# DriverMosfet_2.net
KiCad netlist of a schematic drawn in EAGLE
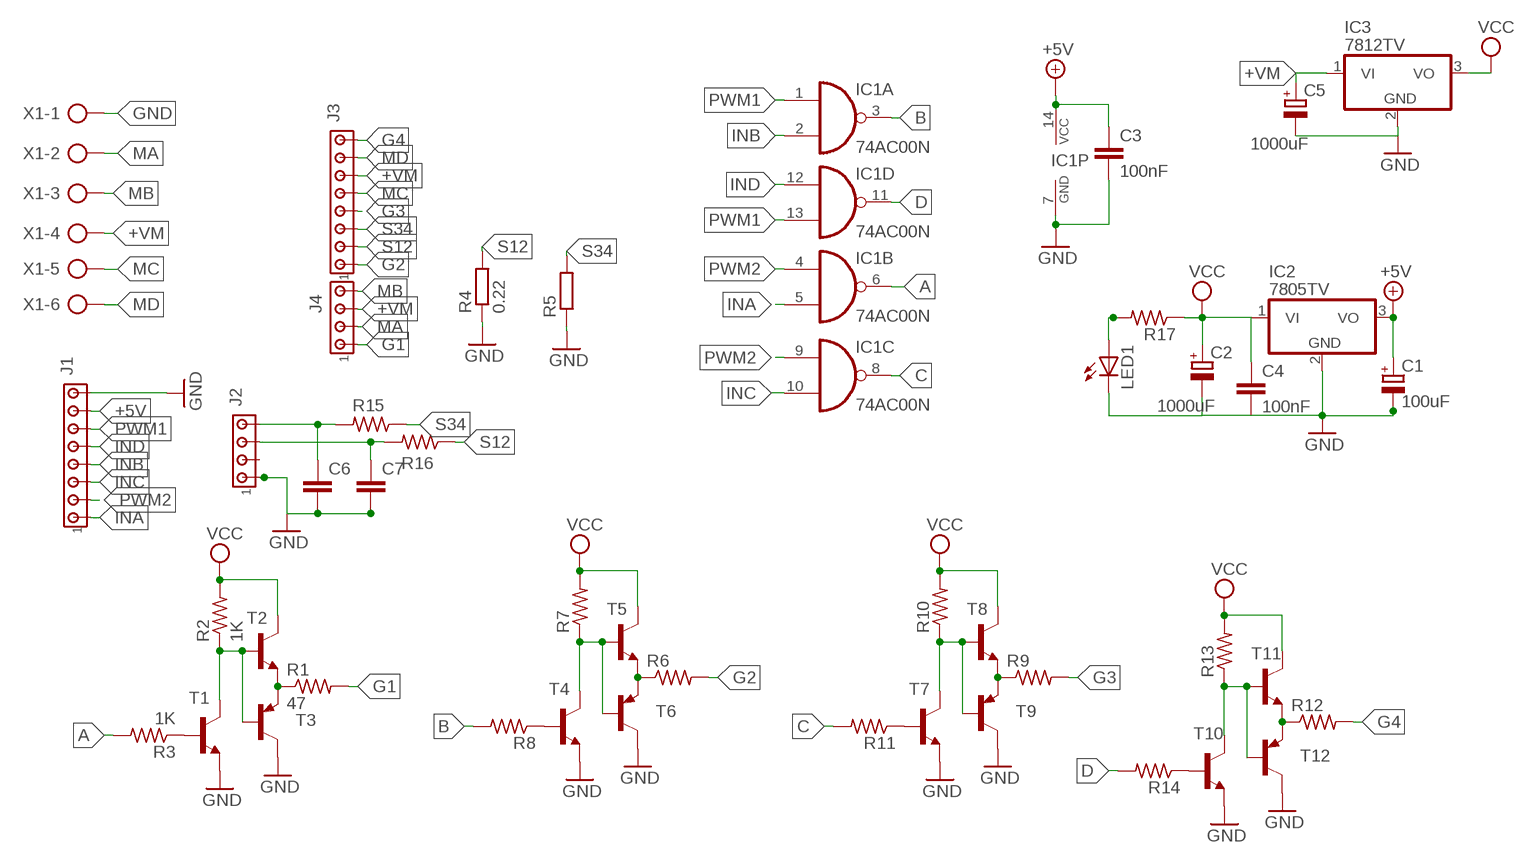
[diagram p0: schematic, sheet 1]

(export (version "E")
  (design (tool "Eeschema 10.0.6"))
  (components
    (comp (ref "C1")
      (value "100uF")
      (footprint "eagle-import:E2,5-6")
      (libsource (lib "eagle-import") (part "CPOL-EUE2.5-6"))
    )
    (comp (ref "C2")
      (value "1000uF")
      (footprint "eagle-import:E2,5-7")
      (libsource (lib "eagle-import") (part "CPOL-EUE2.5-7"))
    )
    (comp (ref "C3")
      (value "100nF")
      (footprint "eagle-import:C050-025X075")
      (libsource (lib "eagle-import") (part "C-EU050-025X075"))
    )
    (comp (ref "C4")
      (value "100nF")
      (footprint "eagle-import:C050-025X075")
      (libsource (lib "eagle-import") (part "C-EU050-025X075"))
    )
    (comp (ref "C5")
      (value "1000uF")
      (footprint "eagle-import:E3,5-10")
      (libsource (lib "eagle-import") (part "CPOL-EUE3.5-10"))
    )
    (comp (ref "C6")
      (value "C-EU025-030X050")
      (footprint "eagle-import:C025-030X050")
      (libsource (lib "eagle-import") (part "C-EU025-030X050"))
    )
    (comp (ref "C7")
      (value "C-EU025-030X050")
      (footprint "eagle-import:C025-030X050")
      (libsource (lib "eagle-import") (part "C-EU025-030X050"))
    )
    (comp (ref "IC1")
      (value "74AC00N")
      (footprint "eagle-import:DIL14")
      (libsource (lib "eagle-import") (part "7400NAC"))
    )
    (comp (ref "IC2")
      (value "7805TV")
      (footprint "eagle-import:TO220V")
      (libsource (lib "eagle-import") (part "78TV05"))
    )
    (comp (ref "IC3")
      (value "7812TV")
      (footprint "eagle-import:TO220V")
      (libsource (lib "eagle-import") (part "78TV12"))
    )
    (comp (ref "J1")
      (value "MTA08-100")
      (footprint "eagle-import:10X08MTA")
      (libsource (lib "eagle-import") (part "MTA08-100"))
    )
    (comp (ref "J2")
      (value "MTA04-100")
      (footprint "eagle-import:10X04MTA")
      (libsource (lib "eagle-import") (part "MTA04-100"))
    )
    (comp (ref "J3")
      (value "MTA08-100")
      (footprint "eagle-import:10X08MTA")
      (libsource (lib "eagle-import") (part "MTA08-100"))
    )
    (comp (ref "J4")
      (value "MTA04-100")
      (footprint "eagle-import:10X04MTA")
      (libsource (lib "eagle-import") (part "MTA04-100"))
    )
    (comp (ref "LED1")
      (value "LED3MM")
      (footprint "eagle-import:LED3MM")
      (libsource (lib "eagle-import") (part "LED3MM"))
    )
    (comp (ref "R1")
      (value "47")
      (footprint "eagle-import:0207_7")
      (libsource (lib "eagle-import") (part "R-US_0207/7"))
    )
    (comp (ref "R2")
      (value "1K")
      (footprint "eagle-import:0207_7")
      (libsource (lib "eagle-import") (part "R-US_0207/7"))
    )
    (comp (ref "R3")
      (value "1K")
      (footprint "eagle-import:0207_7")
      (libsource (lib "eagle-import") (part "R-US_0207/7"))
    )
    (comp (ref "R4")
      (value "0.22")
      (footprint "eagle-import:P0613_15")
      (libsource (lib "eagle-import") (part "R-EU_0613/15"))
    )
    (comp (ref "R5")
      (value "R-EU_0414/15")
      (footprint "eagle-import:0414_15")
      (libsource (lib "eagle-import") (part "R-EU_0414/15"))
    )
    (comp (ref "R6")
      (value "R-US_0207/7")
      (footprint "eagle-import:0207_7")
      (libsource (lib "eagle-import") (part "R-US_0207/7"))
    )
    (comp (ref "R7")
      (value "R-US_0207/7")
      (footprint "eagle-import:0207_7")
      (libsource (lib "eagle-import") (part "R-US_0207/7"))
    )
    (comp (ref "R8")
      (value "R-US_0207/7")
      (footprint "eagle-import:0207_7")
      (libsource (lib "eagle-import") (part "R-US_0207/7"))
    )
    (comp (ref "R9")
      (value "R-US_0207/7")
      (footprint "eagle-import:0207_7")
      (libsource (lib "eagle-import") (part "R-US_0207/7"))
    )
    (comp (ref "R10")
      (value "R-US_0207/7")
      (footprint "eagle-import:0207_7")
      (libsource (lib "eagle-import") (part "R-US_0207/7"))
    )
    (comp (ref "R11")
      (value "R-US_0207/7")
      (footprint "eagle-import:0207_7")
      (libsource (lib "eagle-import") (part "R-US_0207/7"))
    )
    (comp (ref "R12")
      (value "R-US_0207/7")
      (footprint "eagle-import:0207_7")
      (libsource (lib "eagle-import") (part "R-US_0207/7"))
    )
    (comp (ref "R13")
      (value "R-US_0207/7")
      (footprint "eagle-import:0207_7")
      (libsource (lib "eagle-import") (part "R-US_0207/7"))
    )
    (comp (ref "R14")
      (value "R-US_0207/7")
      (footprint "eagle-import:0207_7")
      (libsource (lib "eagle-import") (part "R-US_0207/7"))
    )
    (comp (ref "R15")
      (value "R-US_0207/7")
      (footprint "eagle-import:0207_7")
      (libsource (lib "eagle-import") (part "R-US_0207/7"))
    )
    (comp (ref "R16")
      (value "R-US_0207/7")
      (footprint "eagle-import:0207_7")
      (libsource (lib "eagle-import") (part "R-US_0207/7"))
    )
    (comp (ref "R17")
      (value "R-US_0207/7")
      (footprint "eagle-import:0207_7")
      (libsource (lib "eagle-import") (part "R-US_0207/7"))
    )
    (comp (ref "T1")
      (value "BC547-NPN-TO92-CBE")
      (footprint "eagle-import:TO92-CBE")
      (libsource (lib "eagle-import") (part "-NPN-TO92-CBEBC547"))
    )
    (comp (ref "T2")
      (value "BC547-NPN-TO92-CBE")
      (footprint "eagle-import:TO92-CBE")
      (libsource (lib "eagle-import") (part "-NPN-TO92-CBEBC547"))
    )
    (comp (ref "T3")
      (value "BC557A-PNP-TO92-EBC")
      (footprint "eagle-import:TO92-EBC")
      (libsource (lib "eagle-import") (part "-PNP-TO92-EBCBC557A"))
    )
    (comp (ref "T4")
      (value "BC547-NPN-TO92-CBE")
      (footprint "eagle-import:TO92-CBE")
      (libsource (lib "eagle-import") (part "-NPN-TO92-CBEBC547"))
    )
    (comp (ref "T5")
      (value "BC547-NPN-TO92-CBE")
      (footprint "eagle-import:TO92-CBE")
      (libsource (lib "eagle-import") (part "-NPN-TO92-CBEBC547"))
    )
    (comp (ref "T6")
      (value "BC557A-PNP-TO92-EBC")
      (footprint "eagle-import:TO92-EBC")
      (libsource (lib "eagle-import") (part "-PNP-TO92-EBCBC557A"))
    )
    (comp (ref "T7")
      (value "BC547-NPN-TO92-CBE")
      (footprint "eagle-import:TO92-CBE")
      (libsource (lib "eagle-import") (part "-NPN-TO92-CBEBC547"))
    )
    (comp (ref "T8")
      (value "BC547-NPN-TO92-CBE")
      (footprint "eagle-import:TO92-CBE")
      (libsource (lib "eagle-import") (part "-NPN-TO92-CBEBC547"))
    )
    (comp (ref "T9")
      (value "BC557A-PNP-TO92-EBC")
      (footprint "eagle-import:TO92-EBC")
      (libsource (lib "eagle-import") (part "-PNP-TO92-EBCBC557A"))
    )
    (comp (ref "T10")
      (value "BC547-NPN-TO92-CBE")
      (footprint "eagle-import:TO92-CBE")
      (libsource (lib "eagle-import") (part "-NPN-TO92-CBEBC547"))
    )
    (comp (ref "T11")
      (value "BC547-NPN-TO92-CBE")
      (footprint "eagle-import:TO92-CBE")
      (libsource (lib "eagle-import") (part "-NPN-TO92-CBEBC547"))
    )
    (comp (ref "T12")
      (value "BC557A-PNP-TO92-EBC")
      (footprint "eagle-import:TO92-EBC")
      (libsource (lib "eagle-import") (part "-PNP-TO92-EBCBC557A"))
    )
    (comp (ref "X1")
      (value "AK500/6-H")
      (footprint "eagle-import:AK500_6-H")
      (libsource (lib "eagle-import") (part "AK500/6-H"))
    )
  )
  (nets
    (net (code "1") (name "+5V") (class "Default")
      (node (ref "C1") (pin "+") (pinfunction "+_+") (pintype "passive"))
      (node (ref "C3") (pin "1") (pinfunction "1_1") (pintype "passive"))
      (node (ref "IC1") (pin "14") (pinfunction "VCC_14") (pintype "power_in"))
      (node (ref "IC2") (pin "3") (pinfunction "VO_3") (pintype "passive"))
      (node (ref "J1") (pin "7") (pinfunction "7_7") (pintype "passive"))
    )
    (net (code "2") (name "+VM") (class "Default")
      (node (ref "C5") (pin "+") (pinfunction "+_+") (pintype "passive"))
      (node (ref "IC3") (pin "1") (pinfunction "VI_1") (pintype "input"))
      (node (ref "J3") (pin "6") (pinfunction "6_6") (pintype "passive"))
      (node (ref "J4") (pin "3") (pinfunction "3_3") (pintype "passive"))
      (node (ref "X1") (pin "4") (pinfunction "KL_4") (pintype "passive"))
    )
    (net (code "3") (name "A") (class "Default")
      (node (ref "IC1") (pin "6") (pinfunction "O_6") (pintype "output"))
      (node (ref "R3") (pin "2") (pinfunction "2_2") (pintype "passive"))
    )
    (net (code "4") (name "B") (class "Default")
      (node (ref "IC1") (pin "3") (pinfunction "O_3") (pintype "output"))
      (node (ref "R8") (pin "2") (pinfunction "2_2") (pintype "passive"))
    )
    (net (code "5") (name "C") (class "Default")
      (node (ref "IC1") (pin "8") (pinfunction "O_8") (pintype "output"))
      (node (ref "R11") (pin "2") (pinfunction "2_2") (pintype "passive"))
    )
    (net (code "6") (name "D") (class "Default")
      (node (ref "IC1") (pin "11") (pinfunction "O_11") (pintype "output"))
      (node (ref "R14") (pin "2") (pinfunction "2_2") (pintype "passive"))
    )
    (net (code "7") (name "G1") (class "Default")
      (node (ref "J4") (pin "1") (pinfunction "1_1") (pintype "passive"))
      (node (ref "R1") (pin "2") (pinfunction "2_2") (pintype "passive"))
    )
    (net (code "8") (name "G2") (class "Default")
      (node (ref "J3") (pin "1") (pinfunction "1_1") (pintype "passive"))
      (node (ref "R6") (pin "2") (pinfunction "2_2") (pintype "passive"))
    )
    (net (code "9") (name "G3") (class "Default")
      (node (ref "J3") (pin "4") (pinfunction "4_4") (pintype "passive"))
      (node (ref "R9") (pin "2") (pinfunction "2_2") (pintype "passive"))
    )
    (net (code "10") (name "G4") (class "Default")
      (node (ref "J3") (pin "8") (pinfunction "8_8") (pintype "passive"))
      (node (ref "R12") (pin "2") (pinfunction "2_2") (pintype "passive"))
    )
    (net (code "11") (name "GND") (class "Default")
      (node (ref "C1") (pin "-") (pinfunction "-_-") (pintype "passive"))
      (node (ref "C2") (pin "-") (pinfunction "-_-") (pintype "passive"))
      (node (ref "C3") (pin "2") (pinfunction "2_2") (pintype "passive"))
      (node (ref "C4") (pin "2") (pinfunction "2_2") (pintype "passive"))
      (node (ref "C5") (pin "-") (pinfunction "-_-") (pintype "passive"))
      (node (ref "C6") (pin "2") (pinfunction "2_2") (pintype "passive"))
      (node (ref "C7") (pin "2") (pinfunction "2_2") (pintype "passive"))
      (node (ref "IC1") (pin "7") (pinfunction "GND_7") (pintype "power_in"))
      (node (ref "IC2") (pin "2") (pinfunction "GND_2") (pintype "passive"))
      (node (ref "IC3") (pin "2") (pinfunction "GND_2") (pintype "passive"))
      (node (ref "J1") (pin "8") (pinfunction "8_8") (pintype "passive"))
      (node (ref "J2") (pin "1") (pinfunction "1_1") (pintype "passive"))
      (node (ref "LED1") (pin "K") (pinfunction "C_K") (pintype "passive"))
      (node (ref "R4") (pin "1") (pinfunction "1_1") (pintype "passive"))
      (node (ref "R5") (pin "1") (pinfunction "1_1") (pintype "passive"))
      (node (ref "T1") (pin "E") (pinfunction "E_E") (pintype "passive"))
      (node (ref "T10") (pin "E") (pinfunction "E_E") (pintype "passive"))
      (node (ref "T12") (pin "C") (pinfunction "C_C") (pintype "passive"))
      (node (ref "T3") (pin "C") (pinfunction "C_C") (pintype "passive"))
      (node (ref "T4") (pin "E") (pinfunction "E_E") (pintype "passive"))
      (node (ref "T6") (pin "C") (pinfunction "C_C") (pintype "passive"))
      (node (ref "T7") (pin "E") (pinfunction "E_E") (pintype "passive"))
      (node (ref "T9") (pin "C") (pinfunction "C_C") (pintype "passive"))
      (node (ref "X1") (pin "1") (pinfunction "KL_1") (pintype "passive"))
    )
    (net (code "12") (name "INA") (class "Default")
      (node (ref "IC1") (pin "5") (pinfunction "I1_5") (pintype "input"))
      (node (ref "J1") (pin "1") (pinfunction "1_1") (pintype "passive"))
    )
    (net (code "13") (name "INB") (class "Default")
      (node (ref "IC1") (pin "2") (pinfunction "I1_2") (pintype "input"))
      (node (ref "J1") (pin "4") (pinfunction "4_4") (pintype "passive"))
    )
    (net (code "14") (name "INC") (class "Default")
      (node (ref "IC1") (pin "10") (pinfunction "I1_10") (pintype "input"))
      (node (ref "J1") (pin "3") (pinfunction "3_3") (pintype "passive"))
    )
    (net (code "15") (name "IND") (class "Default")
      (node (ref "IC1") (pin "12") (pinfunction "I0_12") (pintype "input"))
      (node (ref "J1") (pin "5") (pinfunction "5_5") (pintype "passive"))
    )
    (net (code "16") (name "MA") (class "Default")
      (node (ref "J4") (pin "2") (pinfunction "2_2") (pintype "passive"))
      (node (ref "X1") (pin "2") (pinfunction "KL_2") (pintype "passive"))
    )
    (net (code "17") (name "MB") (class "Default")
      (node (ref "J4") (pin "4") (pinfunction "4_4") (pintype "passive"))
      (node (ref "X1") (pin "3") (pinfunction "KL_3") (pintype "passive"))
    )
    (net (code "18") (name "MC") (class "Default")
      (node (ref "J3") (pin "5") (pinfunction "5_5") (pintype "passive"))
      (node (ref "X1") (pin "5") (pinfunction "KL_5") (pintype "passive"))
    )
    (net (code "19") (name "MD") (class "Default")
      (node (ref "J3") (pin "7") (pinfunction "7_7") (pintype "passive"))
      (node (ref "X1") (pin "6") (pinfunction "KL_6") (pintype "passive"))
    )
    (net (code "20") (name "Net-(C6-Pad1)") (class "Default")
      (node (ref "C6") (pin "1") (pinfunction "1_1") (pintype "passive"))
      (node (ref "J2") (pin "4") (pinfunction "4_4") (pintype "passive"))
      (node (ref "R15") (pin "2") (pinfunction "2_2") (pintype "passive"))
    )
    (net (code "21") (name "Net-(C7-Pad1)") (class "Default")
      (node (ref "C7") (pin "1") (pinfunction "1_1") (pintype "passive"))
      (node (ref "J2") (pin "3") (pinfunction "3_3") (pintype "passive"))
      (node (ref "R16") (pin "2") (pinfunction "2_2") (pintype "passive"))
    )
    (net (code "22") (name "Net-(LED1-PadA)") (class "Default")
      (node (ref "LED1") (pin "A") (pinfunction "A_A") (pintype "passive"))
      (node (ref "R17") (pin "2") (pinfunction "2_2") (pintype "passive"))
    )
    (net (code "23") (name "Net-(R1-Pad1)") (class "Default")
      (node (ref "R1") (pin "1") (pinfunction "1_1") (pintype "passive"))
      (node (ref "T2") (pin "E") (pinfunction "E_E") (pintype "passive"))
      (node (ref "T3") (pin "E") (pinfunction "E_E") (pintype "passive"))
    )
    (net (code "24") (name "Net-(R2-Pad1)") (class "Default")
      (node (ref "R2") (pin "1") (pinfunction "1_1") (pintype "passive"))
      (node (ref "T1") (pin "C") (pinfunction "C_C") (pintype "passive"))
      (node (ref "T2") (pin "B") (pinfunction "B_B") (pintype "passive"))
      (node (ref "T3") (pin "B") (pinfunction "B_B") (pintype "passive"))
    )
    (net (code "25") (name "Net-(R3-Pad1)") (class "Default")
      (node (ref "R3") (pin "1") (pinfunction "1_1") (pintype "passive"))
      (node (ref "T1") (pin "B") (pinfunction "B_B") (pintype "passive"))
    )
    (net (code "26") (name "Net-(R6-Pad1)") (class "Default")
      (node (ref "R6") (pin "1") (pinfunction "1_1") (pintype "passive"))
      (node (ref "T5") (pin "E") (pinfunction "E_E") (pintype "passive"))
      (node (ref "T6") (pin "E") (pinfunction "E_E") (pintype "passive"))
    )
    (net (code "27") (name "Net-(R7-Pad1)") (class "Default")
      (node (ref "R7") (pin "1") (pinfunction "1_1") (pintype "passive"))
      (node (ref "T4") (pin "C") (pinfunction "C_C") (pintype "passive"))
      (node (ref "T5") (pin "B") (pinfunction "B_B") (pintype "passive"))
      (node (ref "T6") (pin "B") (pinfunction "B_B") (pintype "passive"))
    )
    (net (code "28") (name "Net-(R8-Pad1)") (class "Default")
      (node (ref "R8") (pin "1") (pinfunction "1_1") (pintype "passive"))
      (node (ref "T4") (pin "B") (pinfunction "B_B") (pintype "passive"))
    )
    (net (code "29") (name "Net-(R9-Pad1)") (class "Default")
      (node (ref "R9") (pin "1") (pinfunction "1_1") (pintype "passive"))
      (node (ref "T8") (pin "E") (pinfunction "E_E") (pintype "passive"))
      (node (ref "T9") (pin "E") (pinfunction "E_E") (pintype "passive"))
    )
    (net (code "30") (name "Net-(R10-Pad1)") (class "Default")
      (node (ref "R10") (pin "1") (pinfunction "1_1") (pintype "passive"))
      (node (ref "T7") (pin "C") (pinfunction "C_C") (pintype "passive"))
      (node (ref "T8") (pin "B") (pinfunction "B_B") (pintype "passive"))
      (node (ref "T9") (pin "B") (pinfunction "B_B") (pintype "passive"))
    )
    (net (code "31") (name "Net-(R11-Pad1)") (class "Default")
      (node (ref "R11") (pin "1") (pinfunction "1_1") (pintype "passive"))
      (node (ref "T7") (pin "B") (pinfunction "B_B") (pintype "passive"))
    )
    (net (code "32") (name "Net-(R12-Pad1)") (class "Default")
      (node (ref "R12") (pin "1") (pinfunction "1_1") (pintype "passive"))
      (node (ref "T11") (pin "E") (pinfunction "E_E") (pintype "passive"))
      (node (ref "T12") (pin "E") (pinfunction "E_E") (pintype "passive"))
    )
    (net (code "33") (name "Net-(R13-Pad1)") (class "Default")
      (node (ref "R13") (pin "1") (pinfunction "1_1") (pintype "passive"))
      (node (ref "T10") (pin "C") (pinfunction "C_C") (pintype "passive"))
      (node (ref "T11") (pin "B") (pinfunction "B_B") (pintype "passive"))
      (node (ref "T12") (pin "B") (pinfunction "B_B") (pintype "passive"))
    )
    (net (code "34") (name "Net-(R14-Pad1)") (class "Default")
      (node (ref "R14") (pin "1") (pinfunction "1_1") (pintype "passive"))
      (node (ref "T10") (pin "B") (pinfunction "B_B") (pintype "passive"))
    )
    (net (code "35") (name "PWM1") (class "Default")
      (node (ref "IC1") (pin "1") (pinfunction "I0_1") (pintype "input"))
      (node (ref "IC1") (pin "13") (pinfunction "I1_13") (pintype "input"))
      (node (ref "J1") (pin "6") (pinfunction "6_6") (pintype "passive"))
    )
    (net (code "36") (name "PWM2") (class "Default")
      (node (ref "IC1") (pin "4") (pinfunction "I0_4") (pintype "input"))
      (node (ref "IC1") (pin "9") (pinfunction "I0_9") (pintype "input"))
      (node (ref "J1") (pin "2") (pinfunction "2_2") (pintype "passive"))
    )
    (net (code "37") (name "S12") (class "Default")
      (node (ref "J3") (pin "2") (pinfunction "2_2") (pintype "passive"))
      (node (ref "R16") (pin "1") (pinfunction "1_1") (pintype "passive"))
      (node (ref "R4") (pin "2") (pinfunction "2_2") (pintype "passive"))
    )
    (net (code "38") (name "S34") (class "Default")
      (node (ref "J3") (pin "3") (pinfunction "3_3") (pintype "passive"))
      (node (ref "R15") (pin "1") (pinfunction "1_1") (pintype "passive"))
      (node (ref "R5") (pin "2") (pinfunction "2_2") (pintype "passive"))
    )
    (net (code "39") (name "VCC") (class "Default")
      (node (ref "C2") (pin "+") (pinfunction "+_+") (pintype "passive"))
      (node (ref "C4") (pin "1") (pinfunction "1_1") (pintype "passive"))
      (node (ref "IC2") (pin "1") (pinfunction "VI_1") (pintype "input"))
      (node (ref "IC3") (pin "3") (pinfunction "VO_3") (pintype "passive"))
      (node (ref "R10") (pin "2") (pinfunction "2_2") (pintype "passive"))
      (node (ref "R13") (pin "2") (pinfunction "2_2") (pintype "passive"))
      (node (ref "R17") (pin "1") (pinfunction "1_1") (pintype "passive"))
      (node (ref "R2") (pin "2") (pinfunction "2_2") (pintype "passive"))
      (node (ref "R7") (pin "2") (pinfunction "2_2") (pintype "passive"))
      (node (ref "T11") (pin "C") (pinfunction "C_C") (pintype "passive"))
      (node (ref "T2") (pin "C") (pinfunction "C_C") (pintype "passive"))
      (node (ref "T5") (pin "C") (pinfunction "C_C") (pintype "passive"))
      (node (ref "T8") (pin "C") (pinfunction "C_C") (pintype "passive"))
    )
    (net (code "40") (name "unconnected-(J2-Pad2)") (class "Default")
      (node (ref "J2") (pin "2") (pinfunction "2_2") (pintype "passive"))
    )
  )
)
